# Cantaloupe.net
KiCad netlist of a schematic drawn in EAGLE
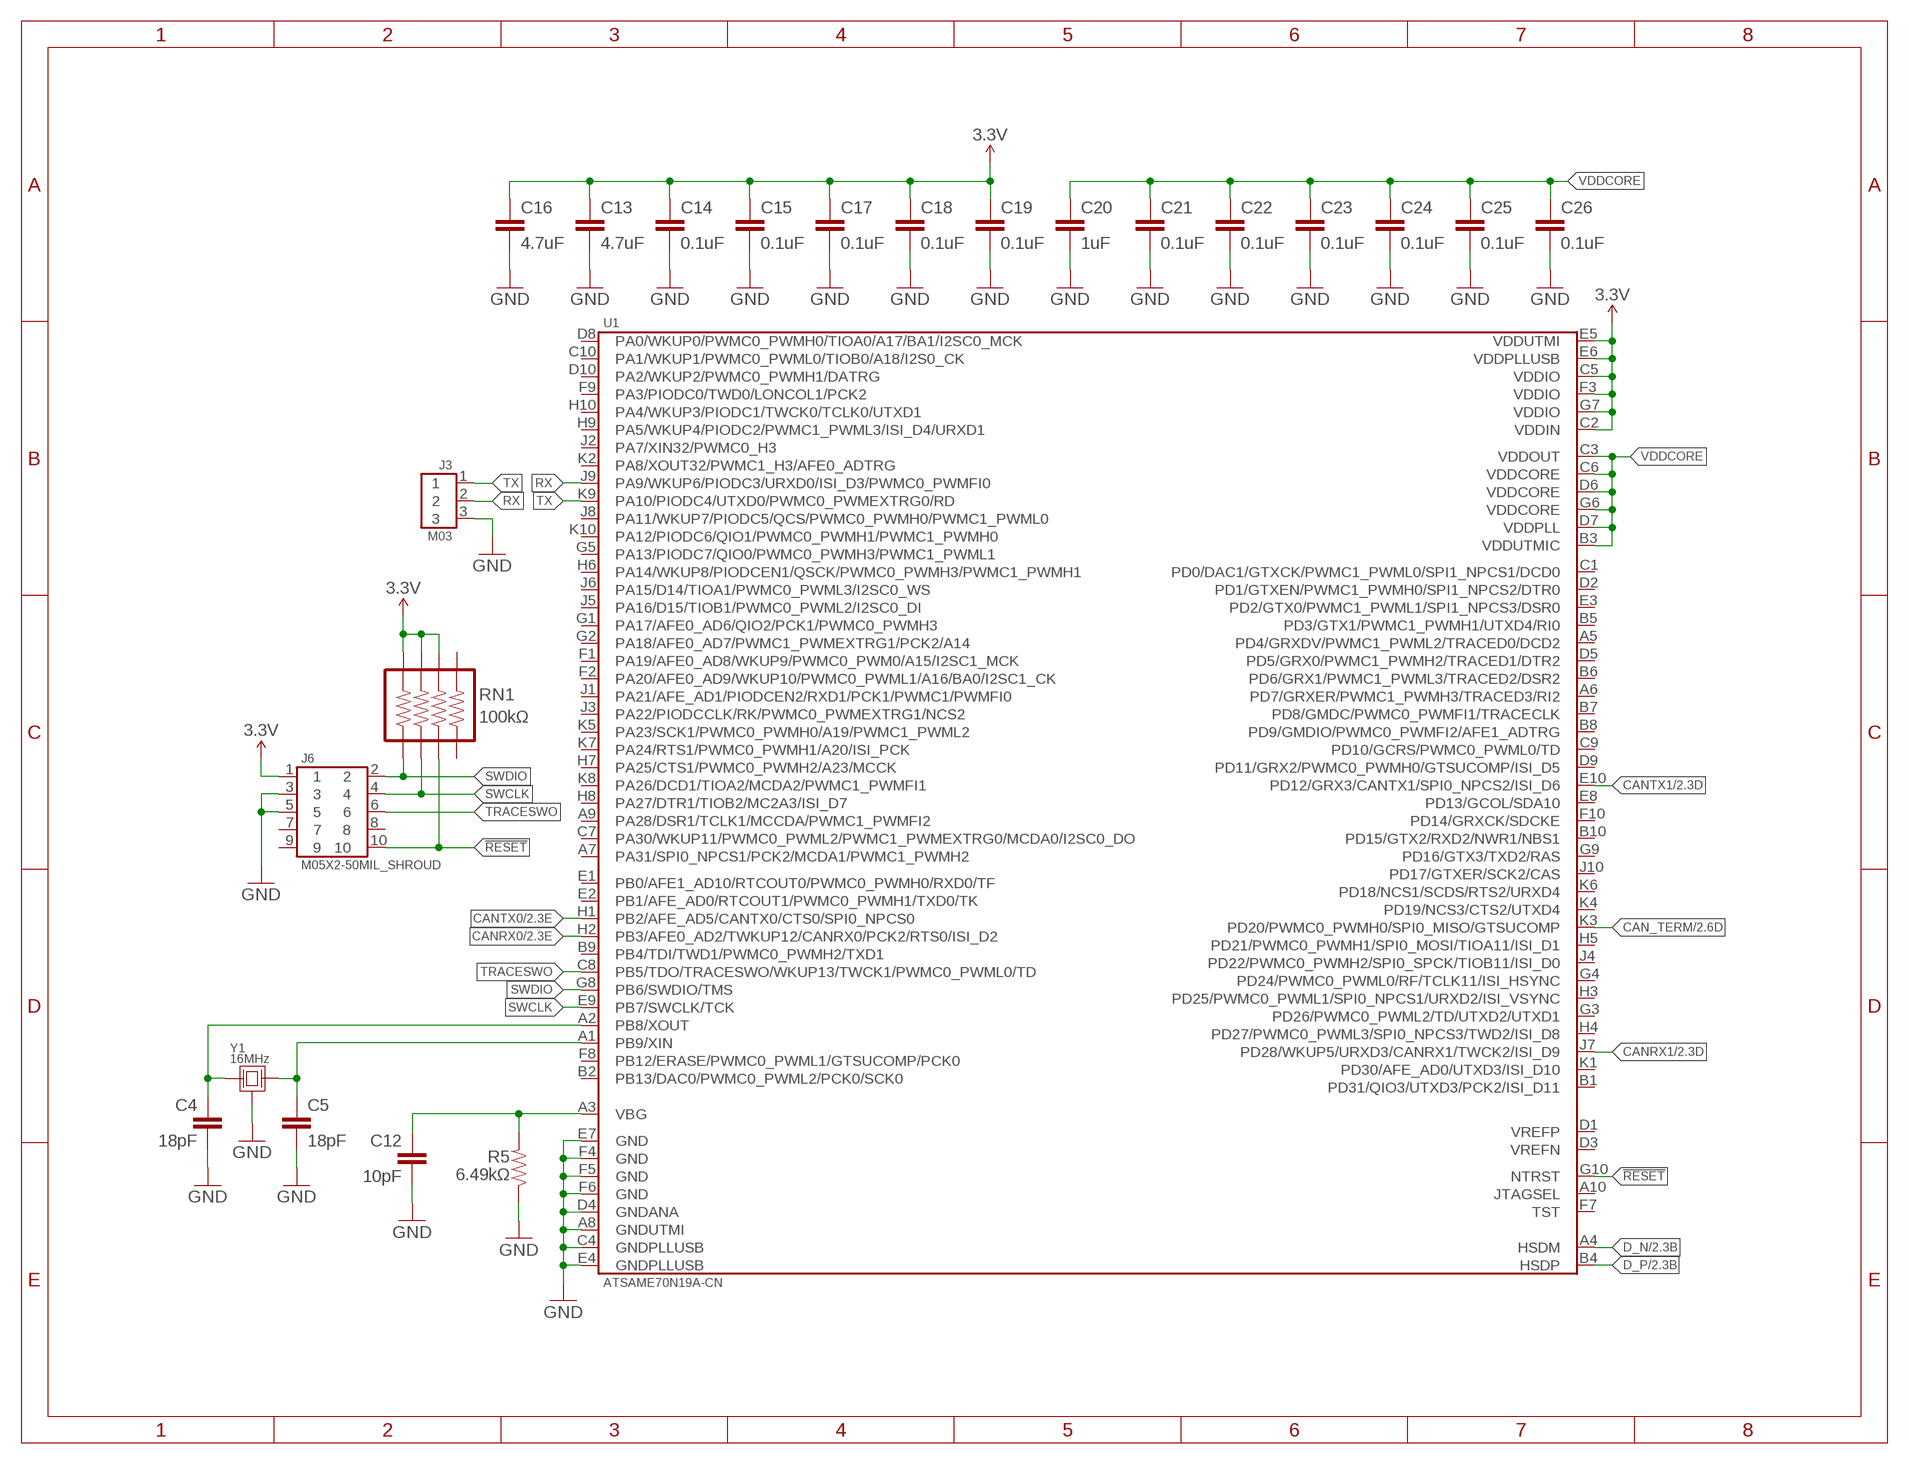
[diagram p0: schematic, sheet 1]
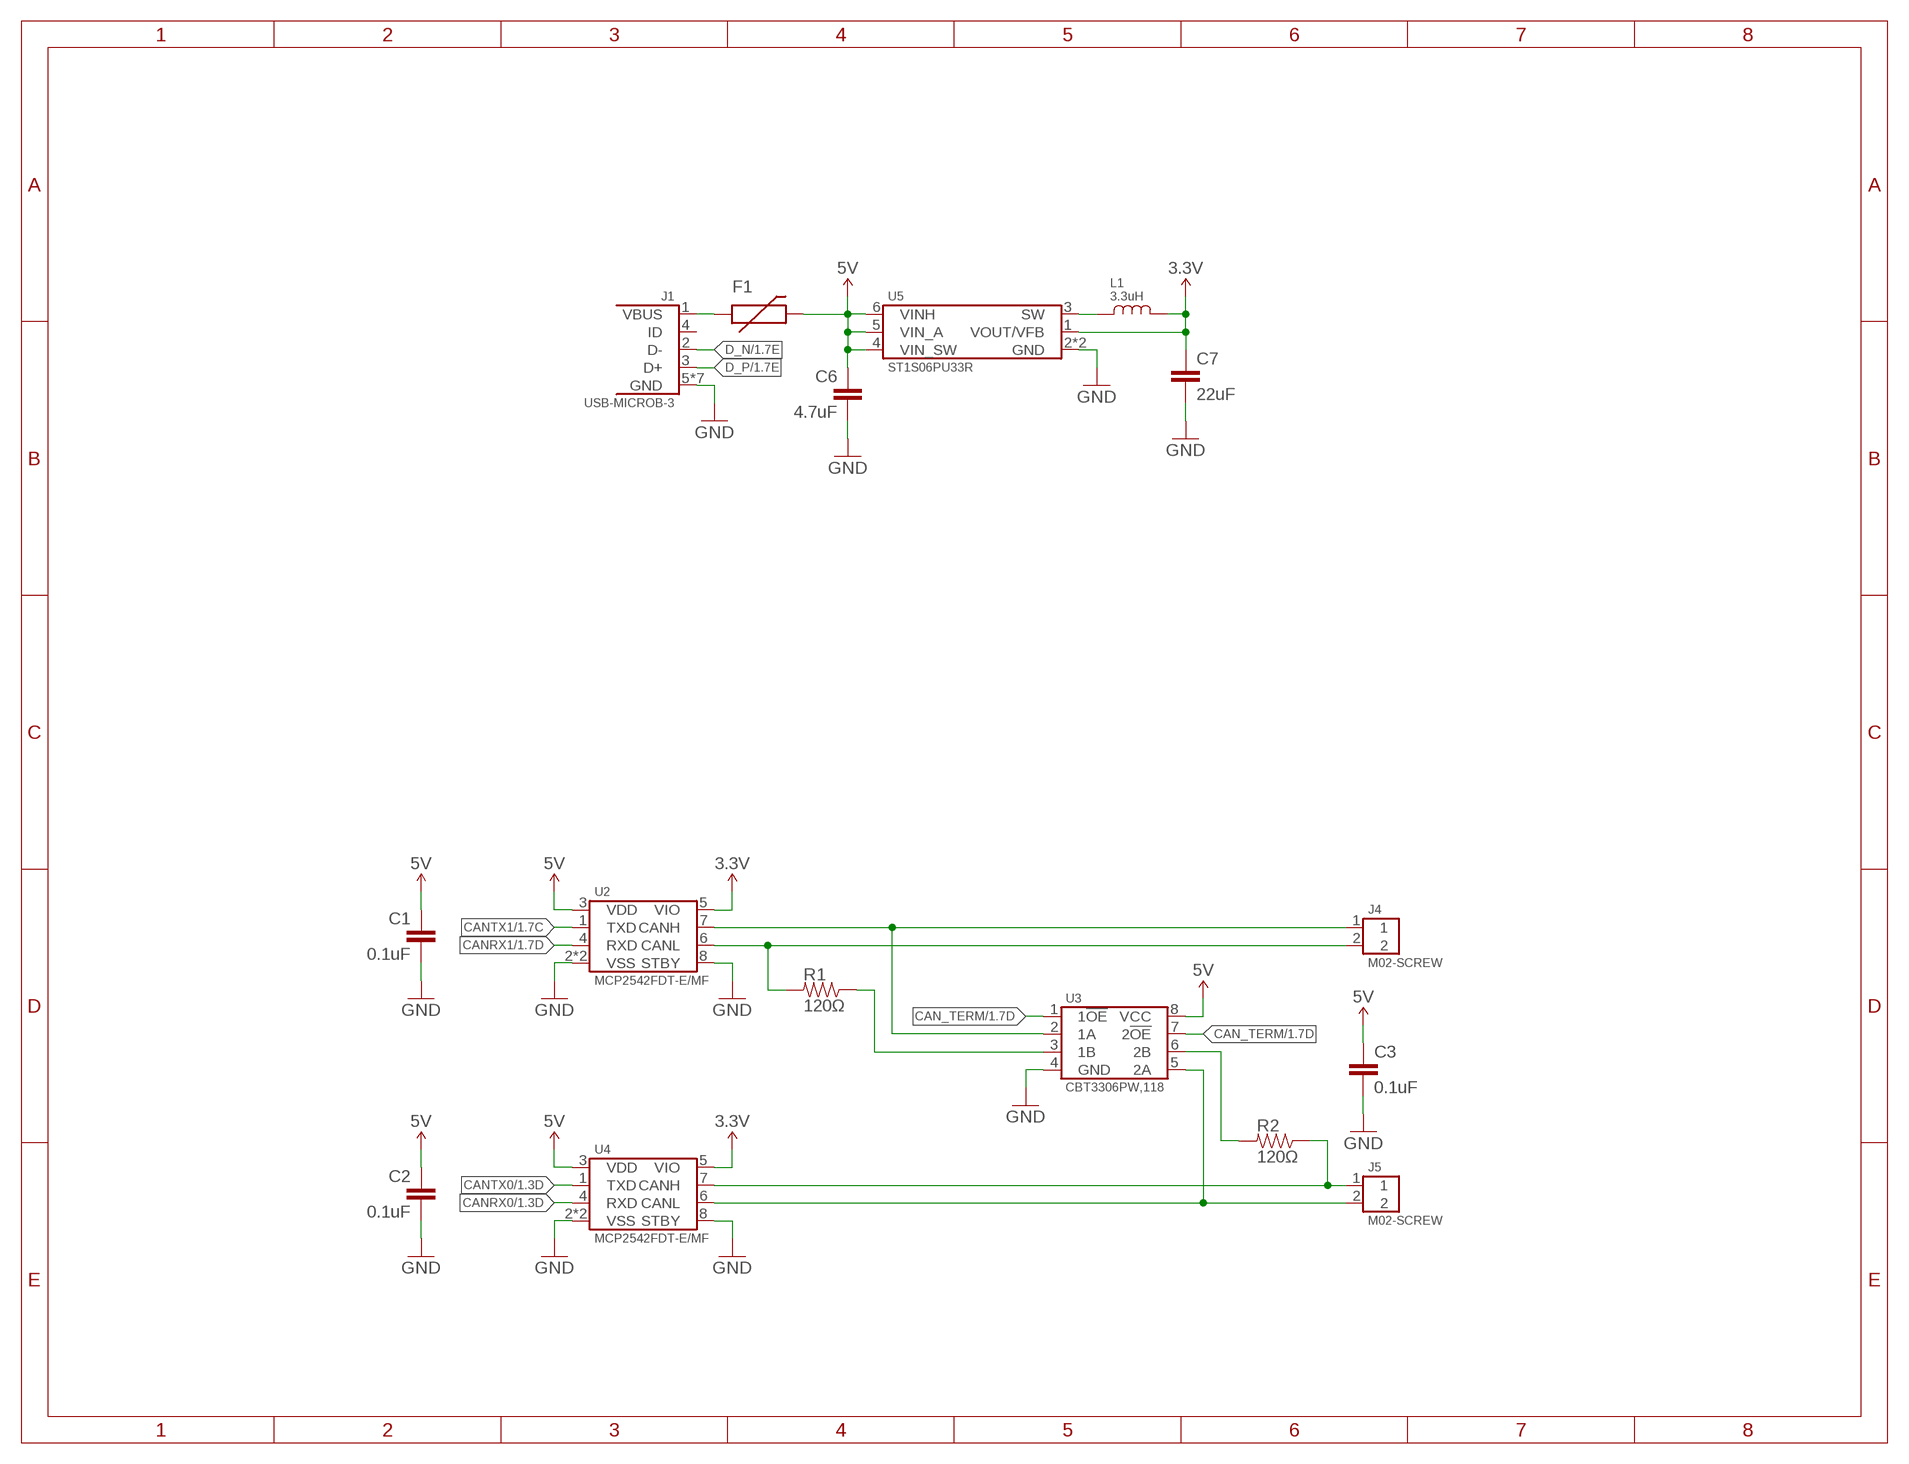
[diagram p1: schematic, sheet 2]

(export (version "E")
  (design (tool "Eeschema 10.0.6"))
  (components
    (comp (ref "C4")
      (value "18pF")
      (footprint "eagle-import:0603-CAP")
      (libsource (lib "eagle-import") (part "CAP-0603"))
    )
    (comp (ref "C5")
      (value "18pF")
      (footprint "eagle-import:0603-CAP")
      (libsource (lib "eagle-import") (part "CAP-0603"))
    )
    (comp (ref "C12")
      (value "10pF")
      (footprint "eagle-import:0603-CAP")
      (libsource (lib "eagle-import") (part "CAP-0603"))
    )
    (comp (ref "C13")
      (value "4.7uF")
      (footprint "eagle-import:0603-CAP")
      (libsource (lib "eagle-import") (part "CAP-0603"))
    )
    (comp (ref "C14")
      (value "0.1uF")
      (footprint "eagle-import:0603-CAP")
      (libsource (lib "eagle-import") (part "CAP-0603"))
    )
    (comp (ref "C15")
      (value "0.1uF")
      (footprint "eagle-import:0603-CAP")
      (libsource (lib "eagle-import") (part "CAP-0603"))
    )
    (comp (ref "C16")
      (value "4.7uF")
      (footprint "eagle-import:0603-CAP")
      (libsource (lib "eagle-import") (part "CAP-0603"))
    )
    (comp (ref "C17")
      (value "0.1uF")
      (footprint "eagle-import:0603-CAP")
      (libsource (lib "eagle-import") (part "CAP-0603"))
    )
    (comp (ref "C18")
      (value "0.1uF")
      (footprint "eagle-import:0603-CAP")
      (libsource (lib "eagle-import") (part "CAP-0603"))
    )
    (comp (ref "C19")
      (value "0.1uF")
      (footprint "eagle-import:0603-CAP")
      (libsource (lib "eagle-import") (part "CAP-0603"))
    )
    (comp (ref "C20")
      (value "1uF")
      (footprint "eagle-import:0603-CAP")
      (libsource (lib "eagle-import") (part "CAP-0603"))
    )
    (comp (ref "C21")
      (value "0.1uF")
      (footprint "eagle-import:0603-CAP")
      (libsource (lib "eagle-import") (part "CAP-0603"))
    )
    (comp (ref "C22")
      (value "0.1uF")
      (footprint "eagle-import:0603-CAP")
      (libsource (lib "eagle-import") (part "CAP-0603"))
    )
    (comp (ref "C23")
      (value "0.1uF")
      (footprint "eagle-import:0603-CAP")
      (libsource (lib "eagle-import") (part "CAP-0603"))
    )
    (comp (ref "C24")
      (value "0.1uF")
      (footprint "eagle-import:0603-CAP")
      (libsource (lib "eagle-import") (part "CAP-0603"))
    )
    (comp (ref "C25")
      (value "0.1uF")
      (footprint "eagle-import:0603-CAP")
      (libsource (lib "eagle-import") (part "CAP-0603"))
    )
    (comp (ref "C26")
      (value "0.1uF")
      (footprint "eagle-import:0603-CAP")
      (libsource (lib "eagle-import") (part "CAP-0603"))
    )
    (comp (ref "J3")
      (value "M03")
      (footprint "eagle-import:M03")
      (libsource (lib "eagle-import") (part "M03"))
    )
    (comp (ref "J6")
      (value "M05X2-50MIL_SHROUD")
      (footprint "eagle-import:M05X2-50MIL-SHROUD")
      (libsource (lib "eagle-import") (part "M05X2-50MIL_SHROUD"))
    )
    (comp (ref "R5")
      (value "6.49kΩ")
      (footprint "eagle-import:0603-CAP")
      (libsource (lib "eagle-import") (part "RESISTOR-0603"))
    )
    (comp (ref "RN1")
      (value "100kΩ")
      (footprint "eagle-import:1206-RESISTOR_ARRAY")
      (libsource (lib "eagle-import") (part "RESISTOR-ARRAY-1206"))
    )
    (comp (ref "U1")
      (value "ATSAME70N19A-CN")
      (footprint "eagle-import:TFBGA-100-9MM")
      (libsource (lib "eagle-import") (part "ATSAME70N19A-CN"))
    )
    (comp (ref "Y1")
      (value "16MHz")
      (footprint "eagle-import:FA-238")
      (libsource (lib "eagle-import") (part "CRYSTAL-3.2X2.5"))
    )
    (comp (ref "C1")
      (value "0.1uF")
      (footprint "eagle-import:0603-CAP")
      (libsource (lib "eagle-import") (part "CAP-0603"))
    )
    (comp (ref "C2")
      (value "0.1uF")
      (footprint "eagle-import:0603-CAP")
      (libsource (lib "eagle-import") (part "CAP-0603"))
    )
    (comp (ref "C3")
      (value "0.1uF")
      (footprint "eagle-import:0603-CAP")
      (libsource (lib "eagle-import") (part "CAP-0603"))
    )
    (comp (ref "C6")
      (value "4.7uF")
      (footprint "eagle-import:0603-CAP")
      (libsource (lib "eagle-import") (part "CAP-0603"))
    )
    (comp (ref "C7")
      (value "22uF")
      (footprint "eagle-import:1206")
      (libsource (lib "eagle-import") (part "CAP-1206"))
    )
    (comp (ref "F1")
      (value "PTC-1206")
      (footprint "eagle-import:1206-PTC")
      (libsource (lib "eagle-import") (part "PTC-1206"))
    )
    (comp (ref "J1")
      (value "USB-MICROB-3")
      (footprint "eagle-import:10118192-0001LF")
      (libsource (lib "eagle-import") (part "USB-MICROB-3"))
    )
    (comp (ref "J4")
      (value "M02-SCREW")
      (footprint "eagle-import:M02-SCREW")
      (libsource (lib "eagle-import") (part "M02-SCREW"))
    )
    (comp (ref "J5")
      (value "M02-SCREW")
      (footprint "eagle-import:M02-SCREW")
      (libsource (lib "eagle-import") (part "M02-SCREW"))
    )
    (comp (ref "L1")
      (value "3.3uH")
      (footprint "eagle-import:1008-INDUCTOR")
      (libsource (lib "eagle-import") (part "INDUCTOR-1008"))
    )
    (comp (ref "R1")
      (value "120Ω")
      (footprint "eagle-import:0603-CAP")
      (libsource (lib "eagle-import") (part "RESISTOR-0603"))
    )
    (comp (ref "R2")
      (value "120Ω")
      (footprint "eagle-import:0603-CAP")
      (libsource (lib "eagle-import") (part "RESISTOR-0603"))
    )
    (comp (ref "U2")
      (value "MCP2542FDT-E/MF")
      (footprint "eagle-import:DFN-8-3X3")
      (libsource (lib "eagle-import") (part "MCP2542FDT-E/MF"))
    )
    (comp (ref "U3")
      (value "CBT3306PW,118")
      (footprint "eagle-import:TSSOP8-4.4MM")
      (libsource (lib "eagle-import") (part "CBT3306PW,118"))
    )
    (comp (ref "U4")
      (value "MCP2542FDT-E/MF")
      (footprint "eagle-import:DFN-8-3X3")
      (libsource (lib "eagle-import") (part "MCP2542FDT-E/MF"))
    )
    (comp (ref "U5")
      (value "ST1S06PU33R")
      (footprint "eagle-import:DFN-6-3MM")
      (libsource (lib "eagle-import") (part "ST1S06XX"))
    )
  )
  (nets
    (net (code "1") (name "3.3V") (class "Default")
      (node (ref "C13") (pin "1") (pinfunction "1_1") (pintype "passive"))
      (node (ref "C14") (pin "1") (pinfunction "1_1") (pintype "passive"))
      (node (ref "C15") (pin "1") (pinfunction "1_1") (pintype "passive"))
      (node (ref "C16") (pin "1") (pinfunction "1_1") (pintype "passive"))
      (node (ref "C17") (pin "1") (pinfunction "1_1") (pintype "passive"))
      (node (ref "C18") (pin "1") (pinfunction "1_1") (pintype "passive"))
      (node (ref "C19") (pin "1") (pinfunction "1_1") (pintype "passive"))
      (node (ref "C7") (pin "1") (pinfunction "1_1") (pintype "passive"))
      (node (ref "J6") (pin "1") (pinfunction "1_1") (pintype "bidirectional"))
      (node (ref "L1") (pin "P$2") (pinfunction "P$2_P$2") (pintype "bidirectional"))
      (node (ref "RN1") (pin "5") (pinfunction "5_5") (pintype "passive"))
      (node (ref "RN1") (pin "6") (pinfunction "6_6") (pintype "passive"))
      (node (ref "RN1") (pin "7") (pinfunction "7_7") (pintype "passive"))
      (node (ref "U1") (pin "C2") (pinfunction "VDDIN_C2") (pintype "bidirectional"))
      (node (ref "U1") (pin "C5") (pinfunction "VDDIO_C5") (pintype "bidirectional"))
      (node (ref "U1") (pin "E5") (pinfunction "VDDUTMI_E5") (pintype "bidirectional"))
      (node (ref "U1") (pin "E6") (pinfunction "VDDPLLUSB_E6") (pintype "bidirectional"))
      (node (ref "U1") (pin "F3") (pinfunction "VDDIO_F3") (pintype "bidirectional"))
      (node (ref "U1") (pin "G7") (pinfunction "VDDIO_G7") (pintype "bidirectional"))
      (node (ref "U2") (pin "5") (pinfunction "VIO_5") (pintype "bidirectional"))
      (node (ref "U4") (pin "5") (pinfunction "VIO_5") (pintype "bidirectional"))
      (node (ref "U5") (pin "1") (pinfunction "VOUT/VFB_1") (pintype "bidirectional"))
    )
    (net (code "2") (name "5V") (class "Default")
      (node (ref "C1") (pin "1") (pinfunction "1_1") (pintype "passive"))
      (node (ref "C2") (pin "1") (pinfunction "1_1") (pintype "passive"))
      (node (ref "C3") (pin "1") (pinfunction "1_1") (pintype "passive"))
      (node (ref "C6") (pin "1") (pinfunction "1_1") (pintype "passive"))
      (node (ref "F1") (pin "P$2") (pinfunction "2_P$2") (pintype "bidirectional"))
      (node (ref "U2") (pin "3") (pinfunction "VDD_3") (pintype "bidirectional"))
      (node (ref "U3") (pin "8") (pinfunction "VCC_8") (pintype "bidirectional"))
      (node (ref "U4") (pin "3") (pinfunction "VDD_3") (pintype "bidirectional"))
      (node (ref "U5") (pin "4") (pinfunction "VIN_SW_4") (pintype "bidirectional"))
      (node (ref "U5") (pin "5") (pinfunction "VIN_A_5") (pintype "bidirectional"))
      (node (ref "U5") (pin "6") (pinfunction "VINH_6") (pintype "bidirectional"))
    )
    (net (code "3") (name "CANRX0") (class "Default")
      (node (ref "U1") (pin "H2") (pinfunction "PB3/AFE0_AD2/TWKUP12/CANRX0/PCK2/RTS0/ISI_D2_H2") (pintype "bidirectional"))
      (node (ref "U4") (pin "4") (pinfunction "RXD_4") (pintype "bidirectional"))
    )
    (net (code "4") (name "CANRX1") (class "Default")
      (node (ref "U1") (pin "J7") (pinfunction "PD28/WKUP5/URXD3/CANRX1/TWCK2/ISI_D9_J7") (pintype "bidirectional"))
      (node (ref "U2") (pin "4") (pinfunction "RXD_4") (pintype "bidirectional"))
    )
    (net (code "5") (name "CANTX0") (class "Default")
      (node (ref "U1") (pin "H1") (pinfunction "PB2/AFE_AD5/CANTX0/CTS0/SPI0_NPCS0_H1") (pintype "bidirectional"))
      (node (ref "U4") (pin "1") (pinfunction "TXD_1") (pintype "bidirectional"))
    )
    (net (code "6") (name "CANTX1") (class "Default")
      (node (ref "U1") (pin "E10") (pinfunction "PD12/GRX3/CANTX1/SPI0_NPCS2/ISI_D6_E10") (pintype "bidirectional"))
      (node (ref "U2") (pin "1") (pinfunction "TXD_1") (pintype "bidirectional"))
    )
    (net (code "7") (name "CAN_TERM") (class "Default")
      (node (ref "U1") (pin "K3") (pinfunction "PD20/PWMC0_PWMH0/SPI0_MISO/GTSUCOMP_K3") (pintype "bidirectional"))
      (node (ref "U3") (pin "1") (pinfunction "1~{OE}_1") (pintype "bidirectional"))
      (node (ref "U3") (pin "7") (pinfunction "2~{OE}_7") (pintype "bidirectional"))
    )
    (net (code "8") (name "D_N") (class "Default")
      (node (ref "J1") (pin "2") (pinfunction "D-_2") (pintype "bidirectional"))
      (node (ref "U1") (pin "A4") (pinfunction "HSDM_A4") (pintype "bidirectional"))
    )
    (net (code "9") (name "D_P") (class "Default")
      (node (ref "J1") (pin "3") (pinfunction "D+_3") (pintype "bidirectional"))
      (node (ref "U1") (pin "B4") (pinfunction "HSDP_B4") (pintype "bidirectional"))
    )
    (net (code "10") (name "GND") (class "Default")
      (node (ref "C1") (pin "2") (pinfunction "2_2") (pintype "passive"))
      (node (ref "C12") (pin "2") (pinfunction "2_2") (pintype "passive"))
      (node (ref "C13") (pin "2") (pinfunction "2_2") (pintype "passive"))
      (node (ref "C14") (pin "2") (pinfunction "2_2") (pintype "passive"))
      (node (ref "C15") (pin "2") (pinfunction "2_2") (pintype "passive"))
      (node (ref "C16") (pin "2") (pinfunction "2_2") (pintype "passive"))
      (node (ref "C17") (pin "2") (pinfunction "2_2") (pintype "passive"))
      (node (ref "C18") (pin "2") (pinfunction "2_2") (pintype "passive"))
      (node (ref "C19") (pin "2") (pinfunction "2_2") (pintype "passive"))
      (node (ref "C2") (pin "2") (pinfunction "2_2") (pintype "passive"))
      (node (ref "C20") (pin "2") (pinfunction "2_2") (pintype "passive"))
      (node (ref "C21") (pin "2") (pinfunction "2_2") (pintype "passive"))
      (node (ref "C22") (pin "2") (pinfunction "2_2") (pintype "passive"))
      (node (ref "C23") (pin "2") (pinfunction "2_2") (pintype "passive"))
      (node (ref "C24") (pin "2") (pinfunction "2_2") (pintype "passive"))
      (node (ref "C25") (pin "2") (pinfunction "2_2") (pintype "passive"))
      (node (ref "C26") (pin "2") (pinfunction "2_2") (pintype "passive"))
      (node (ref "C3") (pin "2") (pinfunction "2_2") (pintype "passive"))
      (node (ref "C4") (pin "2") (pinfunction "2_2") (pintype "passive"))
      (node (ref "C5") (pin "2") (pinfunction "2_2") (pintype "passive"))
      (node (ref "C6") (pin "2") (pinfunction "2_2") (pintype "passive"))
      (node (ref "C7") (pin "2") (pinfunction "2_2") (pintype "passive"))
      (node (ref "J1") (pin "5") (pinfunction "GND_5") (pintype "bidirectional"))
      (node (ref "J1") (pin "P$10") (pinfunction "GND_P$10") (pintype "bidirectional"))
      (node (ref "J1") (pin "P$11") (pinfunction "GND_P$11") (pintype "bidirectional"))
      (node (ref "J1") (pin "P$6") (pinfunction "GND_P$6") (pintype "bidirectional"))
      (node (ref "J1") (pin "P$7") (pinfunction "GND_P$7") (pintype "bidirectional"))
      (node (ref "J1") (pin "P$8") (pinfunction "GND_P$8") (pintype "bidirectional"))
      (node (ref "J1") (pin "P$9") (pinfunction "GND_P$9") (pintype "bidirectional"))
      (node (ref "J3") (pin "3") (pinfunction "3_3") (pintype "bidirectional"))
      (node (ref "J6") (pin "3") (pinfunction "3_3") (pintype "bidirectional"))
      (node (ref "J6") (pin "5") (pinfunction "5_5") (pintype "bidirectional"))
      (node (ref "R5") (pin "1") (pinfunction "1_1") (pintype "passive"))
      (node (ref "U1") (pin "A8") (pinfunction "GNDUTMI_A8") (pintype "bidirectional"))
      (node (ref "U1") (pin "C4") (pinfunction "GNDPLLUSB_C4") (pintype "bidirectional"))
      (node (ref "U1") (pin "D4") (pinfunction "GNDANA_D4") (pintype "bidirectional"))
      (node (ref "U1") (pin "E4") (pinfunction "GNDPLLUSB_E4") (pintype "bidirectional"))
      (node (ref "U1") (pin "E7") (pinfunction "GND_E7") (pintype "bidirectional"))
      (node (ref "U1") (pin "F4") (pinfunction "GND_F4") (pintype "bidirectional"))
      (node (ref "U1") (pin "F5") (pinfunction "GND_F5") (pintype "bidirectional"))
      (node (ref "U1") (pin "F6") (pinfunction "GND_F6") (pintype "bidirectional"))
      (node (ref "U2") (pin "2") (pinfunction "VSS_2") (pintype "bidirectional"))
      (node (ref "U2") (pin "8") (pinfunction "STBY_8") (pintype "bidirectional"))
      (node (ref "U2") (pin "PAD") (pinfunction "VSS_PAD") (pintype "bidirectional"))
      (node (ref "U3") (pin "4") (pinfunction "GND_4") (pintype "bidirectional"))
      (node (ref "U4") (pin "2") (pinfunction "VSS_2") (pintype "bidirectional"))
      (node (ref "U4") (pin "8") (pinfunction "STBY_8") (pintype "bidirectional"))
      (node (ref "U4") (pin "PAD") (pinfunction "VSS_PAD") (pintype "bidirectional"))
      (node (ref "U5") (pin "2") (pinfunction "GND_2") (pintype "bidirectional"))
      (node (ref "U5") (pin "PAD") (pinfunction "GND_PAD") (pintype "bidirectional"))
      (node (ref "Y1") (pin "2") (pinfunction "GND_2") (pintype "bidirectional"))
      (node (ref "Y1") (pin "4") (pinfunction "GND_4") (pintype "bidirectional"))
    )
    (net (code "11") (name "Net-(F1-1)") (class "Default")
      (node (ref "F1") (pin "P$1") (pinfunction "1_P$1") (pintype "bidirectional"))
      (node (ref "J1") (pin "1") (pinfunction "VBUS_1") (pintype "bidirectional"))
    )
    (net (code "12") (name "Net-(U1-PB8{slash}XOUT)") (class "Default")
      (node (ref "C4") (pin "1") (pinfunction "1_1") (pintype "passive"))
      (node (ref "U1") (pin "A2") (pinfunction "PB8/XOUT_A2") (pintype "bidirectional"))
      (node (ref "Y1") (pin "1") (pinfunction "1_1") (pintype "bidirectional"))
    )
    (net (code "13") (name "Net-(U1-PB9{slash}XIN)") (class "Default")
      (node (ref "C5") (pin "1") (pinfunction "1_1") (pintype "passive"))
      (node (ref "U1") (pin "A1") (pinfunction "PB9/XIN_A1") (pintype "bidirectional"))
      (node (ref "Y1") (pin "3") (pinfunction "2_3") (pintype "bidirectional"))
    )
    (net (code "14") (name "Net-(U1-VBG)") (class "Default")
      (node (ref "C12") (pin "1") (pinfunction "1_1") (pintype "passive"))
      (node (ref "R5") (pin "2") (pinfunction "2_2") (pintype "passive"))
      (node (ref "U1") (pin "A3") (pinfunction "VBG_A3") (pintype "bidirectional"))
    )
    (net (code "15") (name "Net-(U2-CANH)") (class "Default")
      (node (ref "J4") (pin "1") (pinfunction "1_1") (pintype "bidirectional"))
      (node (ref "U2") (pin "7") (pinfunction "CANH_7") (pintype "bidirectional"))
      (node (ref "U3") (pin "2") (pinfunction "1A_2") (pintype "bidirectional"))
    )
    (net (code "16") (name "Net-(U2-CANL)") (class "Default")
      (node (ref "J4") (pin "2") (pinfunction "2_2") (pintype "bidirectional"))
      (node (ref "R1") (pin "2") (pinfunction "2_2") (pintype "passive"))
      (node (ref "U2") (pin "6") (pinfunction "CANL_6") (pintype "bidirectional"))
    )
    (net (code "17") (name "Net-(U3-1B)") (class "Default")
      (node (ref "R1") (pin "1") (pinfunction "1_1") (pintype "passive"))
      (node (ref "U3") (pin "3") (pinfunction "1B_3") (pintype "bidirectional"))
    )
    (net (code "18") (name "Net-(U3-2A)") (class "Default")
      (node (ref "J5") (pin "2") (pinfunction "2_2") (pintype "bidirectional"))
      (node (ref "U3") (pin "5") (pinfunction "2A_5") (pintype "bidirectional"))
      (node (ref "U4") (pin "6") (pinfunction "CANL_6") (pintype "bidirectional"))
    )
    (net (code "19") (name "Net-(U3-2B)") (class "Default")
      (node (ref "R2") (pin "2") (pinfunction "2_2") (pintype "passive"))
      (node (ref "U3") (pin "6") (pinfunction "2B_6") (pintype "bidirectional"))
    )
    (net (code "20") (name "Net-(U4-CANH)") (class "Default")
      (node (ref "J5") (pin "1") (pinfunction "1_1") (pintype "bidirectional"))
      (node (ref "R2") (pin "1") (pinfunction "1_1") (pintype "passive"))
      (node (ref "U4") (pin "7") (pinfunction "CANH_7") (pintype "bidirectional"))
    )
    (net (code "21") (name "Net-(U5-SW)") (class "Default")
      (node (ref "L1") (pin "P$1") (pinfunction "P$1_P$1") (pintype "bidirectional"))
      (node (ref "U5") (pin "3") (pinfunction "SW_3") (pintype "bidirectional"))
    )
    (net (code "22") (name "RX") (class "Default")
      (node (ref "J3") (pin "2") (pinfunction "2_2") (pintype "bidirectional"))
      (node (ref "U1") (pin "J9") (pinfunction "PA9/WKUP6/PIODC3/URXD0/ISI_D3/PWMC0_PWMFI0_J9") (pintype "bidirectional"))
    )
    (net (code "23") (name "SWCLK") (class "Default")
      (node (ref "J6") (pin "4") (pinfunction "4_4") (pintype "bidirectional"))
      (node (ref "RN1") (pin "2") (pinfunction "2_2") (pintype "passive"))
      (node (ref "U1") (pin "E9") (pinfunction "PB7/SWCLK/TCK_E9") (pintype "bidirectional"))
    )
    (net (code "24") (name "SWDIO") (class "Default")
      (node (ref "J6") (pin "2") (pinfunction "2_2") (pintype "bidirectional"))
      (node (ref "RN1") (pin "1") (pinfunction "1_1") (pintype "passive"))
      (node (ref "U1") (pin "G8") (pinfunction "PB6/SWDIO/TMS_G8") (pintype "bidirectional"))
    )
    (net (code "25") (name "TRACESWO") (class "Default")
      (node (ref "J6") (pin "6") (pinfunction "6_6") (pintype "bidirectional"))
      (node (ref "U1") (pin "C8") (pinfunction "PB5/TDO/TRACESWO/WKUP13/TWCK1/PWMC0_PWML0/TD_C8") (pintype "bidirectional"))
    )
    (net (code "26") (name "TX") (class "Default")
      (node (ref "J3") (pin "1") (pinfunction "1_1") (pintype "bidirectional"))
      (node (ref "U1") (pin "K9") (pinfunction "PA10/PIODC4/UTXD0/PWMC0_PWMEXTRG0/RD_K9") (pintype "bidirectional"))
    )
    (net (code "27") (name "VDDCORE") (class "Default")
      (node (ref "C20") (pin "1") (pinfunction "1_1") (pintype "passive"))
      (node (ref "C21") (pin "1") (pinfunction "1_1") (pintype "passive"))
      (node (ref "C22") (pin "1") (pinfunction "1_1") (pintype "passive"))
      (node (ref "C23") (pin "1") (pinfunction "1_1") (pintype "passive"))
      (node (ref "C24") (pin "1") (pinfunction "1_1") (pintype "passive"))
      (node (ref "C25") (pin "1") (pinfunction "1_1") (pintype "passive"))
      (node (ref "C26") (pin "1") (pinfunction "1_1") (pintype "passive"))
      (node (ref "U1") (pin "B3") (pinfunction "VDDUTMIC_B3") (pintype "bidirectional"))
      (node (ref "U1") (pin "C3") (pinfunction "VDDOUT_C3") (pintype "bidirectional"))
      (node (ref "U1") (pin "C6") (pinfunction "VDDCORE_C6") (pintype "bidirectional"))
      (node (ref "U1") (pin "D6") (pinfunction "VDDCORE_D6") (pintype "bidirectional"))
      (node (ref "U1") (pin "D7") (pinfunction "VDDPLL_D7") (pintype "bidirectional"))
      (node (ref "U1") (pin "G6") (pinfunction "VDDCORE_G6") (pintype "bidirectional"))
    )
    (net (code "28") (name "unconnected-(J1-ID-Pad4)") (class "Default")
      (node (ref "J1") (pin "4") (pinfunction "ID_4") (pintype "bidirectional"))
    )
    (net (code "29") (name "unconnected-(J6-Pad7)") (class "Default")
      (node (ref "J6") (pin "7") (pinfunction "7_7") (pintype "bidirectional"))
    )
    (net (code "30") (name "unconnected-(J6-Pad8)") (class "Default")
      (node (ref "J6") (pin "8") (pinfunction "8_8") (pintype "bidirectional"))
    )
    (net (code "31") (name "unconnected-(J6-Pad9)") (class "Default")
      (node (ref "J6") (pin "9") (pinfunction "9_9") (pintype "bidirectional"))
    )
    (net (code "32") (name "unconnected-(RN1-Pad4)") (class "Default")
      (node (ref "RN1") (pin "4") (pinfunction "4_4") (pintype "passive"))
    )
    (net (code "33") (name "unconnected-(RN1-Pad8)") (class "Default")
      (node (ref "RN1") (pin "8") (pinfunction "8_8") (pintype "passive"))
    )
    (net (code "34") (name "unconnected-(U1-JTAGSEL-PadA10)") (class "Default")
      (node (ref "U1") (pin "A10") (pinfunction "JTAGSEL_A10") (pintype "bidirectional"))
    )
    (net (code "35") (name "unconnected-(U1-PA0{slash}WKUP0{slash}PWMC0_PWMH0{slash}TIOA0{slash}A17{slash}BA1{slash}I2SC0_MCK-PadD8)") (class "Default")
      (node (ref "U1") (pin "D8") (pinfunction "PA0/WKUP0/PWMC0_PWMH0/TIOA0/A17/BA1/I2SC0_MCK_D8") (pintype "bidirectional"))
    )
    (net (code "36") (name "unconnected-(U1-PA1{slash}WKUP1{slash}PWMC0_PWML0{slash}TIOB0{slash}A18{slash}I2S0_CK-PadC10)") (class "Default")
      (node (ref "U1") (pin "C10") (pinfunction "PA1/WKUP1/PWMC0_PWML0/TIOB0/A18/I2S0_CK_C10") (pintype "bidirectional"))
    )
    (net (code "37") (name "unconnected-(U1-PA2{slash}WKUP2{slash}PWMC0_PWMH1{slash}DATRG-PadD10)") (class "Default")
      (node (ref "U1") (pin "D10") (pinfunction "PA2/WKUP2/PWMC0_PWMH1/DATRG_D10") (pintype "bidirectional"))
    )
    (net (code "38") (name "unconnected-(U1-PA3{slash}PIODC0{slash}TWD0{slash}LONCOL1{slash}PCK2-PadF9)") (class "Default")
      (node (ref "U1") (pin "F9") (pinfunction "PA3/PIODC0/TWD0/LONCOL1/PCK2_F9") (pintype "bidirectional"))
    )
    (net (code "39") (name "unconnected-(U1-PA4{slash}WKUP3{slash}PIODC1{slash}TWCK0{slash}TCLK0{slash}UTXD1-PadH10)") (class "Default")
      (node (ref "U1") (pin "H10") (pinfunction "PA4/WKUP3/PIODC1/TWCK0/TCLK0/UTXD1_H10") (pintype "bidirectional"))
    )
    (net (code "40") (name "unconnected-(U1-PA5{slash}WKUP4{slash}PIODC2{slash}PWMC1_PWML3{slash}ISI_D4{slash}URXD1-PadH9)") (class "Default")
      (node (ref "U1") (pin "H9") (pinfunction "PA5/WKUP4/PIODC2/PWMC1_PWML3/ISI_D4/URXD1_H9") (pintype "bidirectional"))
    )
    (net (code "41") (name "unconnected-(U1-PA7{slash}XIN32{slash}PWMC0_H3-PadJ2)") (class "Default")
      (node (ref "U1") (pin "J2") (pinfunction "PA7/XIN32/PWMC0_H3_J2") (pintype "bidirectional"))
    )
    (net (code "42") (name "unconnected-(U1-PA8{slash}XOUT32{slash}PWMC1_H3{slash}AFE0_ADTRG-PadK2)") (class "Default")
      (node (ref "U1") (pin "K2") (pinfunction "PA8/XOUT32/PWMC1_H3/AFE0_ADTRG_K2") (pintype "bidirectional"))
    )
    (net (code "43") (name "unconnected-(U1-PA11{slash}WKUP7{slash}PIODC5{slash}QCS{slash}PWMC0_PWMH0{slash}PWMC1_PWML0-PadJ8)") (class "Default")
      (node (ref "U1") (pin "J8") (pinfunction "PA11/WKUP7/PIODC5/QCS/PWMC0_PWMH0/PWMC1_PWML0_J8") (pintype "bidirectional"))
    )
    (net (code "44") (name "unconnected-(U1-PA12{slash}PIODC6{slash}QIO1{slash}PWMC0_PWMH1{slash}PWMC1_PWMH0-PadK10)") (class "Default")
      (node (ref "U1") (pin "K10") (pinfunction "PA12/PIODC6/QIO1/PWMC0_PWMH1/PWMC1_PWMH0_K10") (pintype "bidirectional"))
    )
    (net (code "45") (name "unconnected-(U1-PA13{slash}PIODC7{slash}QIO0{slash}PWMC0_PWMH3{slash}PWMC1_PWML1-PadG5)") (class "Default")
      (node (ref "U1") (pin "G5") (pinfunction "PA13/PIODC7/QIO0/PWMC0_PWMH3/PWMC1_PWML1_G5") (pintype "bidirectional"))
    )
    (net (code "46") (name "unconnected-(U1-PA14{slash}WKUP8{slash}PIODCEN1{slash}QSCK{slash}PWMC0_PWMH3{slash}PWMC1_PWMH1-PadH6)") (class "Default")
      (node (ref "U1") (pin "H6") (pinfunction "PA14/WKUP8/PIODCEN1/QSCK/PWMC0_PWMH3/PWMC1_PWMH1_H6") (pintype "bidirectional"))
    )
    (net (code "47") (name "unconnected-(U1-PA15{slash}D14{slash}TIOA1{slash}PWMC0_PWML3{slash}I2SC0_WS-PadJ6)") (class "Default")
      (node (ref "U1") (pin "J6") (pinfunction "PA15/D14/TIOA1/PWMC0_PWML3/I2SC0_WS_J6") (pintype "bidirectional"))
    )
    (net (code "48") (name "unconnected-(U1-PA16{slash}D15{slash}TIOB1{slash}PWMC0_PWML2{slash}I2SC0_DI-PadJ5)") (class "Default")
      (node (ref "U1") (pin "J5") (pinfunction "PA16/D15/TIOB1/PWMC0_PWML2/I2SC0_DI_J5") (pintype "bidirectional"))
    )
    (net (code "49") (name "unconnected-(U1-PA17{slash}AFE0_AD6{slash}QIO2{slash}PCK1{slash}PWMC0_PWMH3-PadG1)") (class "Default")
      (node (ref "U1") (pin "G1") (pinfunction "PA17/AFE0_AD6/QIO2/PCK1/PWMC0_PWMH3_G1") (pintype "bidirectional"))
    )
    (net (code "50") (name "unconnected-(U1-PA18{slash}AFE0_AD7{slash}PWMC1_PWMEXTRG1{slash}PCK2{slash}A14-PadG2)") (class "Default")
      (node (ref "U1") (pin "G2") (pinfunction "PA18/AFE0_AD7/PWMC1_PWMEXTRG1/PCK2/A14_G2") (pintype "bidirectional"))
    )
    (net (code "51") (name "unconnected-(U1-PA19{slash}AFE0_AD8{slash}WKUP9{slash}PWMC0_PWM0{slash}A15{slash}I2SC1_MCK-PadF1)") (class "Default")
      (node (ref "U1") (pin "F1") (pinfunction "PA19/AFE0_AD8/WKUP9/PWMC0_PWM0/A15/I2SC1_MCK_F1") (pintype "bidirectional"))
    )
    (net (code "52") (name "unconnected-(U1-PA20{slash}AFE0_AD9{slash}WKUP10{slash}PWMC0_PWML1{slash}A16{slash}BA0{slash}I2SC1_CK-PadF2)") (class "Default")
      (node (ref "U1") (pin "F2") (pinfunction "PA20/AFE0_AD9/WKUP10/PWMC0_PWML1/A16/BA0/I2SC1_CK_F2") (pintype "bidirectional"))
    )
    (net (code "53") (name "unconnected-(U1-PA21{slash}AFE_AD1{slash}PIODCEN2{slash}RXD1{slash}PCK1{slash}PWMC1{slash}PWMFI0-PadJ1)") (class "Default")
      (node (ref "U1") (pin "J1") (pinfunction "PA21/AFE_AD1/PIODCEN2/RXD1/PCK1/PWMC1/PWMFI0_J1") (pintype "bidirectional"))
    )
    (net (code "54") (name "unconnected-(U1-PA22{slash}PIODCCLK{slash}RK{slash}PWMC0_PWMEXTRG1{slash}NCS2-PadJ3)") (class "Default")
      (node (ref "U1") (pin "J3") (pinfunction "PA22/PIODCCLK/RK/PWMC0_PWMEXTRG1/NCS2_J3") (pintype "bidirectional"))
    )
    (net (code "55") (name "unconnected-(U1-PA23{slash}SCK1{slash}PWMC0_PWMH0{slash}A19{slash}PWMC1_PWML2-PadK5)") (class "Default")
      (node (ref "U1") (pin "K5") (pinfunction "PA23/SCK1/PWMC0_PWMH0/A19/PWMC1_PWML2_K5") (pintype "bidirectional"))
    )
    (net (code "56") (name "unconnected-(U1-PA24{slash}RTS1{slash}PWMC0_PWMH1{slash}A20{slash}ISI_PCK-PadK7)") (class "Default")
      (node (ref "U1") (pin "K7") (pinfunction "PA24/RTS1/PWMC0_PWMH1/A20/ISI_PCK_K7") (pintype "bidirectional"))
    )
    (net (code "57") (name "unconnected-(U1-PA25{slash}CTS1{slash}PWMC0_PWMH2{slash}A23{slash}MCCK-PadH7)") (class "Default")
      (node (ref "U1") (pin "H7") (pinfunction "PA25/CTS1/PWMC0_PWMH2/A23/MCCK_H7") (pintype "bidirectional"))
    )
    (net (code "58") (name "unconnected-(U1-PA26{slash}DCD1{slash}TIOA2{slash}MCDA2{slash}PWMC1_PWMFI1-PadK8)") (class "Default")
      (node (ref "U1") (pin "K8") (pinfunction "PA26/DCD1/TIOA2/MCDA2/PWMC1_PWMFI1_K8") (pintype "bidirectional"))
    )
    (net (code "59") (name "unconnected-(U1-PA27{slash}DTR1{slash}TIOB2{slash}MC2A3{slash}ISI_D7-PadH8)") (class "Default")
      (node (ref "U1") (pin "H8") (pinfunction "PA27/DTR1/TIOB2/MC2A3/ISI_D7_H8") (pintype "bidirectional"))
    )
    (net (code "60") (name "unconnected-(U1-PA28{slash}DSR1{slash}TCLK1{slash}MCCDA{slash}PWMC1_PWMFI2-PadA9)") (class "Default")
      (node (ref "U1") (pin "A9") (pinfunction "PA28/DSR1/TCLK1/MCCDA/PWMC1_PWMFI2_A9") (pintype "bidirectional"))
    )
    (net (code "61") (name "unconnected-(U1-PA30{slash}WKUP11{slash}PWMC0_PWML2{slash}PWMC1_PWMEXTRG0{slash}MCDA0{slash}I2SC0_DO-PadC7)") (class "Default")
      (node (ref "U1") (pin "C7") (pinfunction "PA30/WKUP11/PWMC0_PWML2/PWMC1_PWMEXTRG0/MCDA0/I2SC0_DO_C7") (pintype "bidirectional"))
    )
    (net (code "62") (name "unconnected-(U1-PA31{slash}SPI0_NPCS1{slash}PCK2{slash}MCDA1{slash}PWMC1_PWMH2-PadA7)") (class "Default")
      (node (ref "U1") (pin "A7") (pinfunction "PA31/SPI0_NPCS1/PCK2/MCDA1/PWMC1_PWMH2_A7") (pintype "bidirectional"))
    )
    (net (code "63") (name "unconnected-(U1-PB0{slash}AFE1_AD10{slash}RTCOUT0{slash}PWMC0_PWMH0{slash}RXD0{slash}TF-PadE1)") (class "Default")
      (node (ref "U1") (pin "E1") (pinfunction "PB0/AFE1_AD10/RTCOUT0/PWMC0_PWMH0/RXD0/TF_E1") (pintype "bidirectional"))
    )
    (net (code "64") (name "unconnected-(U1-PB1{slash}AFE_AD0{slash}RTCOUT1{slash}PWMC0_PWMH1{slash}TXD0{slash}TK-PadE2)") (class "Default")
      (node (ref "U1") (pin "E2") (pinfunction "PB1/AFE_AD0/RTCOUT1/PWMC0_PWMH1/TXD0/TK_E2") (pintype "bidirectional"))
    )
    (net (code "65") (name "unconnected-(U1-PB4{slash}TDI{slash}TWD1{slash}PWMC0_PWMH2{slash}TXD1-PadB9)") (class "Default")
      (node (ref "U1") (pin "B9") (pinfunction "PB4/TDI/TWD1/PWMC0_PWMH2/TXD1_B9") (pintype "bidirectional"))
    )
    (net (code "66") (name "unconnected-(U1-PB12{slash}ERASE{slash}PWMC0_PWML1{slash}GTSUCOMP{slash}PCK0-PadF8)") (class "Default")
      (node (ref "U1") (pin "F8") (pinfunction "PB12/ERASE/PWMC0_PWML1/GTSUCOMP/PCK0_F8") (pintype "bidirectional"))
    )
    (net (code "67") (name "unconnected-(U1-PB13{slash}DAC0{slash}PWMC0_PWML2{slash}PCK0{slash}SCK0-PadB2)") (class "Default")
      (node (ref "U1") (pin "B2") (pinfunction "PB13/DAC0/PWMC0_PWML2/PCK0/SCK0_B2") (pintype "bidirectional"))
    )
    (net (code "68") (name "unconnected-(U1-PD0{slash}DAC1{slash}GTXCK{slash}PWMC1_PWML0{slash}SPI1_NPCS1{slash}DCD0-PadC1)") (class "Default")
      (node (ref "U1") (pin "C1") (pinfunction "PD0/DAC1/GTXCK/PWMC1_PWML0/SPI1_NPCS1/DCD0_C1") (pintype "bidirectional"))
    )
    (net (code "69") (name "unconnected-(U1-PD1{slash}GTXEN{slash}PWMC1_PWMH0{slash}SPI1_NPCS2{slash}DTR0-PadD2)") (class "Default")
      (node (ref "U1") (pin "D2") (pinfunction "PD1/GTXEN/PWMC1_PWMH0/SPI1_NPCS2/DTR0_D2") (pintype "bidirectional"))
    )
    (net (code "70") (name "unconnected-(U1-PD2{slash}GTX0{slash}PWMC1_PWML1{slash}SPI1_NPCS3{slash}DSR0-PadE3)") (class "Default")
      (node (ref "U1") (pin "E3") (pinfunction "PD2/GTX0/PWMC1_PWML1/SPI1_NPCS3/DSR0_E3") (pintype "bidirectional"))
    )
    (net (code "71") (name "unconnected-(U1-PD3{slash}GTX1{slash}PWMC1_PWMH1{slash}UTXD4{slash}RI0-PadB5)") (class "Default")
      (node (ref "U1") (pin "B5") (pinfunction "PD3/GTX1/PWMC1_PWMH1/UTXD4/RI0_B5") (pintype "bidirectional"))
    )
    (net (code "72") (name "unconnected-(U1-PD4{slash}GRXDV{slash}PWMC1_PWML2{slash}TRACED0{slash}DCD2-PadA5)") (class "Default")
      (node (ref "U1") (pin "A5") (pinfunction "PD4/GRXDV/PWMC1_PWML2/TRACED0/DCD2_A5") (pintype "bidirectional"))
    )
    (net (code "73") (name "unconnected-(U1-PD5{slash}GRX0{slash}PWMC1_PWMH2{slash}TRACED1{slash}DTR2-PadD5)") (class "Default")
      (node (ref "U1") (pin "D5") (pinfunction "PD5/GRX0/PWMC1_PWMH2/TRACED1/DTR2_D5") (pintype "bidirectional"))
    )
    (net (code "74") (name "unconnected-(U1-PD6{slash}GRX1{slash}PWMC1_PWML3{slash}TRACED2{slash}DSR2-PadB6)") (class "Default")
      (node (ref "U1") (pin "B6") (pinfunction "PD6/GRX1/PWMC1_PWML3/TRACED2/DSR2_B6") (pintype "bidirectional"))
    )
    (net (code "75") (name "unconnected-(U1-PD7{slash}GRXER{slash}PWMC1_PWMH3{slash}TRACED3{slash}RI2-PadA6)") (class "Default")
      (node (ref "U1") (pin "A6") (pinfunction "PD7/GRXER/PWMC1_PWMH3/TRACED3/RI2_A6") (pintype "bidirectional"))
    )
    (net (code "76") (name "unconnected-(U1-PD8{slash}GMDC{slash}PWMC0_PWMFI1{slash}TRACECLK-PadB7)") (class "Default")
      (node (ref "U1") (pin "B7") (pinfunction "PD8/GMDC/PWMC0_PWMFI1/TRACECLK_B7") (pintype "bidirectional"))
    )
    (net (code "77") (name "unconnected-(U1-PD9{slash}GMDIO{slash}PWMC0_PWMFI2{slash}AFE1_ADTRG-PadB8)") (class "Default")
      (node (ref "U1") (pin "B8") (pinfunction "PD9/GMDIO/PWMC0_PWMFI2/AFE1_ADTRG_B8") (pintype "bidirectional"))
    )
    (net (code "78") (name "unconnected-(U1-PD10{slash}GCRS{slash}PWMC0_PWML0{slash}TD-PadC9)") (class "Default")
      (node (ref "U1") (pin "C9") (pinfunction "PD10/GCRS/PWMC0_PWML0/TD_C9") (pintype "bidirectional"))
    )
    (net (code "79") (name "unconnected-(U1-PD11{slash}GRX2{slash}PWMC0_PWMH0{slash}GTSUCOMP{slash}ISI_D5-PadD9)") (class "Default")
      (node (ref "U1") (pin "D9") (pinfunction "PD11/GRX2/PWMC0_PWMH0/GTSUCOMP/ISI_D5_D9") (pintype "bidirectional"))
    )
    (net (code "80") (name "unconnected-(U1-PD13{slash}GCOL{slash}SDA10-PadE8)") (class "Default")
      (node (ref "U1") (pin "E8") (pinfunction "PD13/GCOL/SDA10_E8") (pintype "bidirectional"))
    )
    (net (code "81") (name "unconnected-(U1-PD14{slash}GRXCK{slash}SDCKE-PadF10)") (class "Default")
      (node (ref "U1") (pin "F10") (pinfunction "PD14/GRXCK/SDCKE_F10") (pintype "bidirectional"))
    )
    (net (code "82") (name "unconnected-(U1-PD15{slash}GTX2{slash}RXD2{slash}NWR1{slash}NBS1-PadB10)") (class "Default")
      (node (ref "U1") (pin "B10") (pinfunction "PD15/GTX2/RXD2/NWR1/NBS1_B10") (pintype "bidirectional"))
    )
    (net (code "83") (name "unconnected-(U1-PD16{slash}GTX3{slash}TXD2{slash}RAS-PadG9)") (class "Default")
      (node (ref "U1") (pin "G9") (pinfunction "PD16/GTX3/TXD2/RAS_G9") (pintype "bidirectional"))
    )
    (net (code "84") (name "unconnected-(U1-PD17{slash}GTXER{slash}SCK2{slash}CAS-PadJ10)") (class "Default")
      (node (ref "U1") (pin "J10") (pinfunction "PD17/GTXER/SCK2/CAS_J10") (pintype "bidirectional"))
    )
    (net (code "85") (name "unconnected-(U1-PD18{slash}NCS1{slash}SCDS{slash}RTS2{slash}URXD4-PadK6)") (class "Default")
      (node (ref "U1") (pin "K6") (pinfunction "PD18/NCS1/SCDS/RTS2/URXD4_K6") (pintype "bidirectional"))
    )
    (net (code "86") (name "unconnected-(U1-PD19{slash}NCS3{slash}CTS2{slash}UTXD4-PadK4)") (class "Default")
      (node (ref "U1") (pin "K4") (pinfunction "PD19/NCS3/CTS2/UTXD4_K4") (pintype "bidirectional"))
    )
    (net (code "87") (name "unconnected-(U1-PD21{slash}PWMC0_PWMH1{slash}SPI0_MOSI{slash}TIOA11{slash}ISI_D1-PadH5)") (class "Default")
      (node (ref "U1") (pin "H5") (pinfunction "PD21/PWMC0_PWMH1/SPI0_MOSI/TIOA11/ISI_D1_H5") (pintype "bidirectional"))
    )
    (net (code "88") (name "unconnected-(U1-PD22{slash}PWMC0_PWMH2{slash}SPI0_SPCK{slash}TIOB11{slash}ISI_D0-PadJ4)") (class "Default")
      (node (ref "U1") (pin "J4") (pinfunction "PD22/PWMC0_PWMH2/SPI0_SPCK/TIOB11/ISI_D0_J4") (pintype "bidirectional"))
    )
    (net (code "89") (name "unconnected-(U1-PD24{slash}PWMC0_PWML0{slash}RF{slash}TCLK11{slash}ISI_HSYNC-PadG4)") (class "Default")
      (node (ref "U1") (pin "G4") (pinfunction "PD24/PWMC0_PWML0/RF/TCLK11/ISI_HSYNC_G4") (pintype "bidirectional"))
    )
    (net (code "90") (name "unconnected-(U1-PD25{slash}PWMC0_PWML1{slash}SPI0_NPCS1{slash}URXD2{slash}ISI_VSYNC-PadH3)") (class "Default")
      (node (ref "U1") (pin "H3") (pinfunction "PD25/PWMC0_PWML1/SPI0_NPCS1/URXD2/ISI_VSYNC_H3") (pintype "bidirectional"))
    )
    (net (code "91") (name "unconnected-(U1-PD26{slash}PWMC0_PWML2{slash}TD{slash}UTXD2{slash}UTXD1-PadG3)") (class "Default")
      (node (ref "U1") (pin "G3") (pinfunction "PD26/PWMC0_PWML2/TD/UTXD2/UTXD1_G3") (pintype "bidirectional"))
    )
    (net (code "92") (name "unconnected-(U1-PD27{slash}PWMC0_PWML3{slash}SPI0_NPCS3{slash}TWD2{slash}ISI_D8-PadH4)") (class "Default")
      (node (ref "U1") (pin "H4") (pinfunction "PD27/PWMC0_PWML3/SPI0_NPCS3/TWD2/ISI_D8_H4") (pintype "bidirectional"))
    )
    (net (code "93") (name "unconnected-(U1-PD30{slash}AFE_AD0{slash}UTXD3{slash}ISI_D10-PadK1)") (class "Default")
      (node (ref "U1") (pin "K1") (pinfunction "PD30/AFE_AD0/UTXD3/ISI_D10_K1") (pintype "bidirectional"))
    )
    (net (code "94") (name "unconnected-(U1-PD31{slash}QIO3{slash}UTXD3{slash}PCK2{slash}ISI_D11-PadB1)") (class "Default")
      (node (ref "U1") (pin "B1") (pinfunction "PD31/QIO3/UTXD3/PCK2/ISI_D11_B1") (pintype "bidirectional"))
    )
    (net (code "95") (name "unconnected-(U1-TST-PadF7)") (class "Default")
      (node (ref "U1") (pin "F7") (pinfunction "TST_F7") (pintype "bidirectional"))
    )
    (net (code "96") (name "unconnected-(U1-VREFN-PadD3)") (class "Default")
      (node (ref "U1") (pin "D3") (pinfunction "VREFN_D3") (pintype "bidirectional"))
    )
    (net (code "97") (name "unconnected-(U1-VREFP-PadD1)") (class "Default")
      (node (ref "U1") (pin "D1") (pinfunction "VREFP_D1") (pintype "bidirectional"))
    )
    (net (code "98") (name "~{RESET}") (class "Default")
      (node (ref "J6") (pin "10") (pinfunction "10_10") (pintype "bidirectional"))
      (node (ref "RN1") (pin "3") (pinfunction "3_3") (pintype "passive"))
      (node (ref "U1") (pin "G10") (pinfunction "NTRST_G10") (pintype "bidirectional"))
    )
  )
)
